# NanoRS485-MySens-v02-25.net
KiCad netlist of a schematic drawn in EAGLE
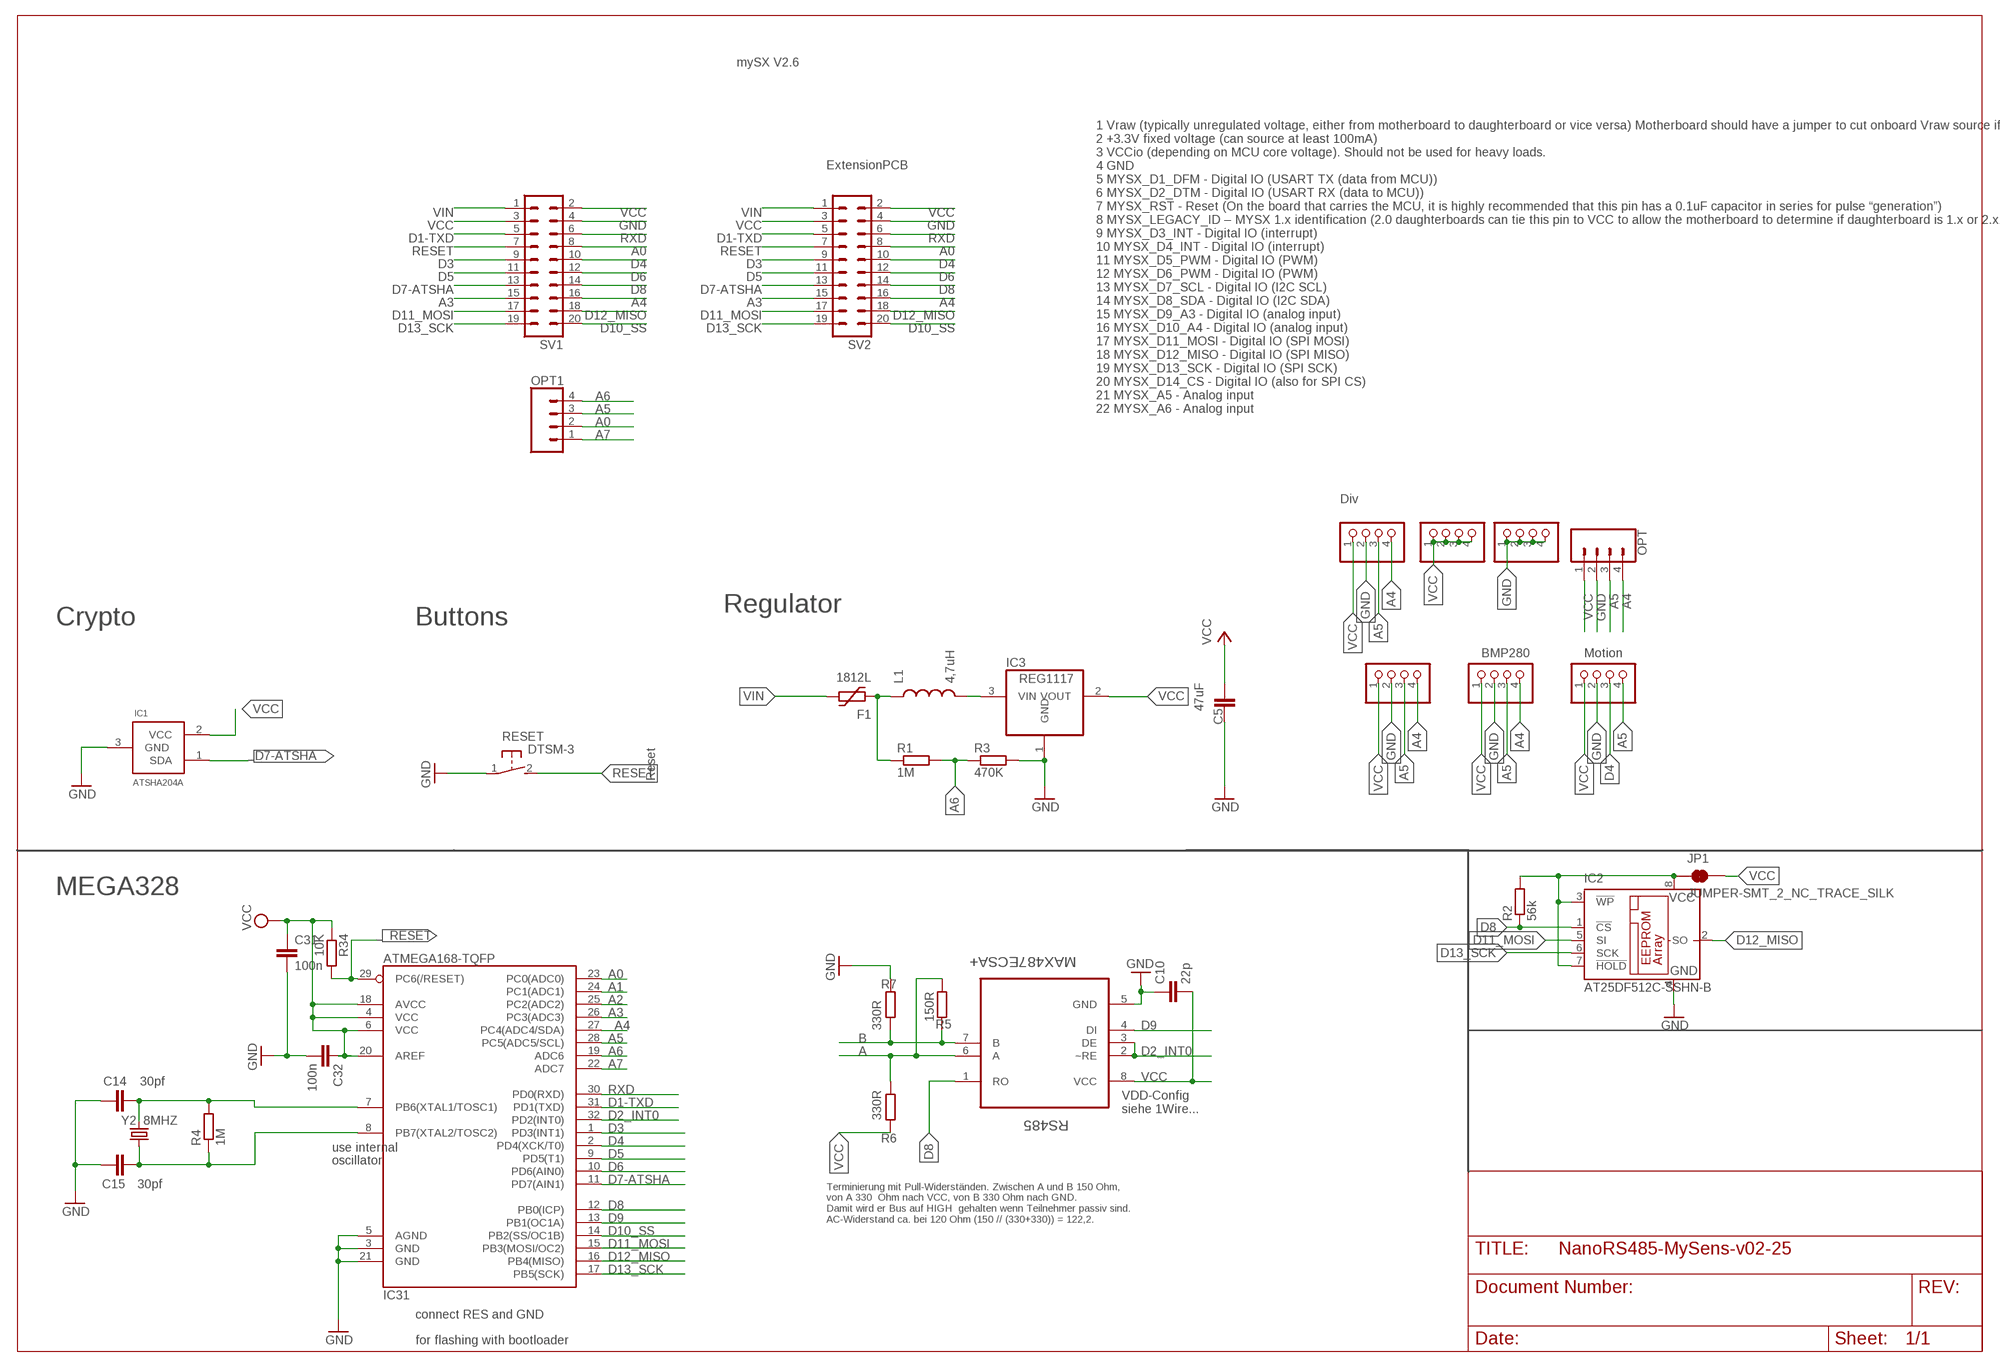
[diagram p0: schematic, sheet 1, part 1 of 2]
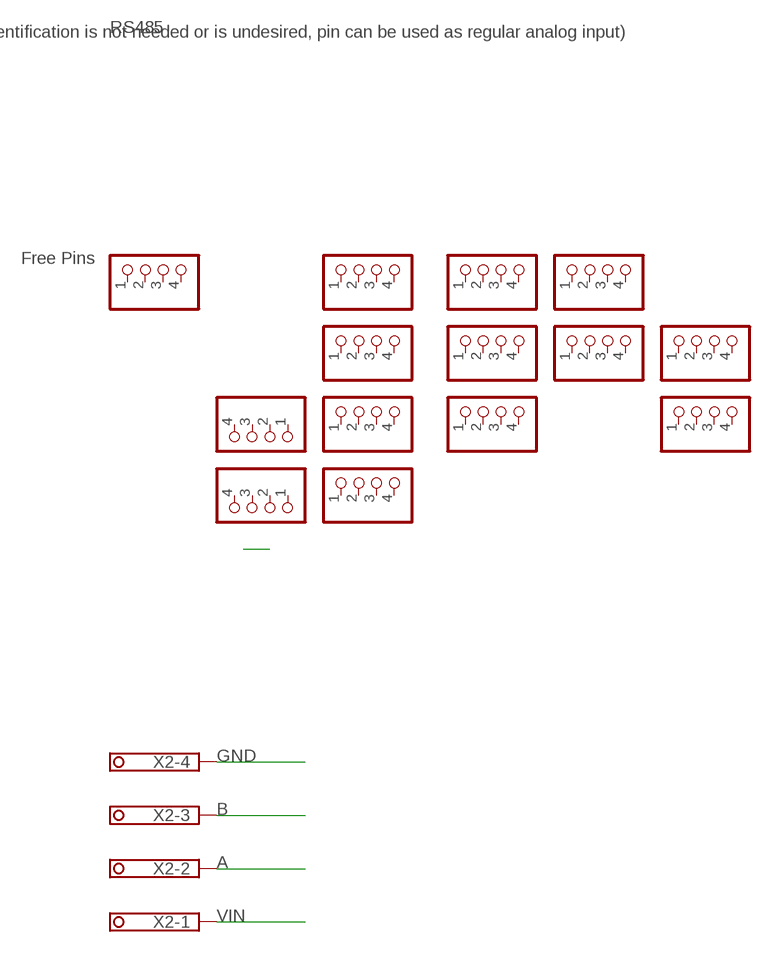
[diagram p1: schematic, sheet 1, part 2 of 2]

(export (version "E")
  (design (tool "Eeschema 10.0.6"))
  (components
    (comp (ref "BH1750")
      (value "PINHD-1X04_2.54-S")
      (footprint "eagle-import:1X04-S")
      (libsource (lib "eagle-import") (part "PINHD-1X04_2.54-S"))
    )
    (comp (ref "C5")
      (value "47uF")
      (footprint "eagle-import:C1210")
      (libsource (lib "eagle-import") (part "C-EUC1210"))
    )
    (comp (ref "C10")
      (value "22p")
      (footprint "eagle-import:C0805")
      (libsource (lib "eagle-import") (part "C-EUC0805"))
    )
    (comp (ref "C14")
      (value "30pf")
      (footprint "eagle-import:0805")
      (libsource (lib "eagle-import") (part "CAP0805"))
    )
    (comp (ref "C15")
      (value "30pf")
      (footprint "eagle-import:0805")
      (libsource (lib "eagle-import") (part "CAP0805"))
    )
    (comp (ref "C31")
      (value "100n")
      (footprint "eagle-import:C0805")
      (libsource (lib "eagle-import") (part "C-EUC0805"))
    )
    (comp (ref "C32")
      (value "100n")
      (footprint "eagle-import:C0805")
      (libsource (lib "eagle-import") (part "C-EUC0805"))
    )
    (comp (ref "F1")
      (value "1812L")
      (footprint "eagle-import:1812L")
      (libsource (lib "eagle-import") (part "1812L"))
    )
    (comp (ref "I2C-1")
      (value "PINHD-1X04_2.54-S")
      (footprint "eagle-import:1X04-S")
      (libsource (lib "eagle-import") (part "PINHD-1X04_2.54-S"))
    )
    (comp (ref "I2C-2")
      (value "PINHD-1X04_2.54-S")
      (footprint "eagle-import:1X04-S")
      (libsource (lib "eagle-import") (part "PINHD-1X04_2.54-S"))
    )
    (comp (ref "IC1")
      (value "ATSHA204A")
      (footprint "eagle-import:SOT23")
      (libsource (lib "eagle-import") (part "ATSHA204A"))
    )
    (comp (ref "IC2")
      (value "AT25DF512C-SSHN-B")
      (footprint "eagle-import:SO-08")
      (fields (field (name "MF") "MICROCHIP") (field (name "MPN") "25AA080/SN"))
      (libsource (lib "eagle-import") (part "25SNAA080"))
    )
    (comp (ref "IC3")
      (value "REG1117")
      (footprint "eagle-import:SOT223")
      (libsource (lib "eagle-import") (part "REG1117"))
    )
    (comp (ref "IC31")
      (value "ATMEGA168-TQFP")
      (footprint "eagle-import:TQFP32-08")
      (libsource (lib "eagle-import") (part "ATMEGA168-TQFP"))
    )
    (comp (ref "JP1")
      (value "JUMPER-SMT_2_NC_TRACE_SILK")
      (footprint "eagle-import:SMT-JUMPER_2_NC_TRACE_SILK")
      (libsource (lib "eagle-import") (part "JUMPER-SMT_2_NC_TRACE_SILK"))
    )
    (comp (ref "JP2")
      (value "PINHD-1X04_2.54-S")
      (footprint "eagle-import:1X04-S")
      (libsource (lib "eagle-import") (part "PINHD-1X04_2.54-S"))
    )
    (comp (ref "JP3")
      (value "PINHD-1X04_2.54-S")
      (footprint "eagle-import:1X04-S")
      (libsource (lib "eagle-import") (part "PINHD-1X04_2.54-S"))
    )
    (comp (ref "JP5")
      (value "PINHD-1X04_2.54-S")
      (footprint "eagle-import:1X04-S")
      (libsource (lib "eagle-import") (part "PINHD-1X04_2.54-S"))
    )
    (comp (ref "JP6")
      (value "PINHD-1X04_2.54-S")
      (footprint "eagle-import:1X04-S")
      (libsource (lib "eagle-import") (part "PINHD-1X04_2.54-S"))
    )
    (comp (ref "JP7")
      (value "PINHD-1X04_2.54-S")
      (footprint "eagle-import:1X04-S")
      (libsource (lib "eagle-import") (part "PINHD-1X04_2.54-S"))
    )
    (comp (ref "JP8")
      (value "PINHD-1X04_2.54-S")
      (footprint "eagle-import:1X04-S")
      (libsource (lib "eagle-import") (part "PINHD-1X04_2.54-S"))
    )
    (comp (ref "JP10")
      (value "PINHD-1X04_2.54-S")
      (footprint "eagle-import:1X04-S")
      (libsource (lib "eagle-import") (part "PINHD-1X04_2.54-S"))
    )
    (comp (ref "JP13")
      (value "PINHD-1X04_2.54-S")
      (footprint "eagle-import:1X04-S")
      (libsource (lib "eagle-import") (part "PINHD-1X04_2.54-S"))
    )
    (comp (ref "JP14")
      (value "PINHD-1X04_2.54-S")
      (footprint "eagle-import:1X04-S")
      (libsource (lib "eagle-import") (part "PINHD-1X04_2.54-S"))
    )
    (comp (ref "JP15")
      (value "PINHD-1X04_2.54-S")
      (footprint "eagle-import:1X04-S")
      (libsource (lib "eagle-import") (part "PINHD-1X04_2.54-S"))
    )
    (comp (ref "JP16")
      (value "PINHD-1X04_2.54-S")
      (footprint "eagle-import:1X04-S")
      (libsource (lib "eagle-import") (part "PINHD-1X04_2.54-S"))
    )
    (comp (ref "JP18")
      (value "PINHD-1X04_2.54-S")
      (footprint "eagle-import:1X04-S")
      (libsource (lib "eagle-import") (part "PINHD-1X04_2.54-S"))
    )
    (comp (ref "JP19")
      (value "PINHD-1X04_2.54-S")
      (footprint "eagle-import:1X04-S")
      (libsource (lib "eagle-import") (part "PINHD-1X04_2.54-S"))
    )
    (comp (ref "JP20")
      (value "PINHD-1X04_2.54-S")
      (footprint "eagle-import:1X04-S")
      (libsource (lib "eagle-import") (part "PINHD-1X04_2.54-S"))
    )
    (comp (ref "JP21")
      (value "PINHD-1X04_2.54-S")
      (footprint "eagle-import:1X04-S")
      (libsource (lib "eagle-import") (part "PINHD-1X04_2.54-S"))
    )
    (comp (ref "JP23")
      (value "PINHD-1X04_2.54-S")
      (footprint "eagle-import:1X04-S")
      (libsource (lib "eagle-import") (part "PINHD-1X04_2.54-S"))
    )
    (comp (ref "L1")
      (value "4,7uH")
      (footprint "eagle-import:0805")
      (libsource (lib "eagle-import") (part "INDUCTOR0805"))
    )
    (comp (ref "MOTION")
      (value "PINHD-1X04_2.54-S")
      (footprint "eagle-import:1X04-S")
      (libsource (lib "eagle-import") (part "PINHD-1X04_2.54-S"))
    )
    (comp (ref "OPT")
      (value "CONN_04")
      (footprint "eagle-import:1X04")
      (libsource (lib "eagle-import") (part "CONN_04"))
    )
    (comp (ref "OPT1")
      (value "CONN_04")
      (footprint "eagle-import:1X04")
      (libsource (lib "eagle-import") (part "CONN_04"))
    )
    (comp (ref "R1")
      (value "1M")
      (footprint "eagle-import:R0805")
      (libsource (lib "eagle-import") (part "R-EU_R0805"))
    )
    (comp (ref "R2")
      (value "56k")
      (footprint "eagle-import:M0805")
      (libsource (lib "eagle-import") (part "resistor_R-EU_M0805"))
    )
    (comp (ref "R3")
      (value "470K")
      (footprint "eagle-import:R0805")
      (libsource (lib "eagle-import") (part "R-EU_R0805"))
    )
    (comp (ref "R4")
      (value "1M")
      (footprint "eagle-import:M0805")
      (libsource (lib "eagle-import") (part "resistor_R-EU_M0805"))
    )
    (comp (ref "R5")
      (value "150R")
      (footprint "eagle-import:R0805")
      (libsource (lib "eagle-import") (part "R-EU_R0805"))
    )
    (comp (ref "R6")
      (value "330R")
      (footprint "eagle-import:R0805")
      (libsource (lib "eagle-import") (part "R-EU_R0805"))
    )
    (comp (ref "R7")
      (value "330R")
      (footprint "eagle-import:R0805")
      (libsource (lib "eagle-import") (part "R-EU_R0805"))
    )
    (comp (ref "R34")
      (value "10K")
      (footprint "eagle-import:R0805")
      (libsource (lib "eagle-import") (part "R-EU_R0805"))
    )
    (comp (ref "RESET")
      (value "DTSM-3")
      (footprint "eagle-import:DTSM-3")
      (libsource (lib "eagle-import") (part "DTSM-3"))
    )
    (comp (ref "RS485")
      (value "MAX487ECSA+")
      (footprint "eagle-import:SOIC127P600X175-8N")
      (libsource (lib "eagle-import") (part "MAX487ECSA+"))
    )
    (comp (ref "SV1")
      (value "MA10-2")
      (footprint "eagle-import:MA10-2")
      (libsource (lib "eagle-import") (part "MA10-2"))
    )
    (comp (ref "SV2")
      (value "MA10-2")
      (footprint "eagle-import:MA10-2")
      (libsource (lib "eagle-import") (part "MA10-2"))
    )
    (comp (ref "X2")
      (value "1751264")
      (footprint "eagle-import:1751264")
      (libsource (lib "eagle-import") (part "1751264"))
    )
    (comp (ref "Y2")
      (value "8MHZ")
      (footprint "eagle-import:CRYSTAL-TXC-7A")
      (libsource (lib "eagle-import") (part "CRYSTALTXC-7A"))
    )
  )
  (nets
    (net (code "1") (name "/A") (class "Default")
      (node (ref "R5") (pin "1") (pinfunction "1_1") (pintype "passive"))
      (node (ref "R6") (pin "2") (pinfunction "2_2") (pintype "passive"))
      (node (ref "RS485") (pin "6") (pinfunction "A_6") (pintype "bidirectional"))
      (node (ref "X2") (pin "2") (pinfunction "K_2") (pintype "passive"))
    )
    (net (code "2") (name "/A0") (class "Default")
      (node (ref "IC31") (pin "23") (pinfunction "PC0(ADC0)_23") (pintype "bidirectional"))
      (node (ref "OPT1") (pin "2") (pinfunction "2_2") (pintype "passive"))
      (node (ref "SV1") (pin "8") (pinfunction "8_8") (pintype "passive"))
      (node (ref "SV2") (pin "8") (pinfunction "8_8") (pintype "passive"))
    )
    (net (code "3") (name "/A1") (class "Default")
      (node (ref "IC31") (pin "24") (pinfunction "PC1(ADC1)_24") (pintype "bidirectional"))
    )
    (net (code "4") (name "/A2") (class "Default")
      (node (ref "IC31") (pin "25") (pinfunction "PC2(ADC2)_25") (pintype "bidirectional"))
    )
    (net (code "5") (name "/A3") (class "Default")
      (node (ref "IC31") (pin "26") (pinfunction "PC3(ADC3)_26") (pintype "bidirectional"))
      (node (ref "SV1") (pin "15") (pinfunction "15_15") (pintype "passive"))
      (node (ref "SV2") (pin "15") (pinfunction "15_15") (pintype "passive"))
    )
    (net (code "6") (name "/A7") (class "Default")
      (node (ref "IC31") (pin "22") (pinfunction "ADC7_22") (pintype "bidirectional"))
      (node (ref "OPT1") (pin "1") (pinfunction "1_1") (pintype "passive"))
    )
    (net (code "7") (name "/B") (class "Default")
      (node (ref "R5") (pin "2") (pinfunction "2_2") (pintype "passive"))
      (node (ref "R7") (pin "1") (pinfunction "1_1") (pintype "passive"))
      (node (ref "RS485") (pin "7") (pinfunction "B_7") (pintype "bidirectional"))
      (node (ref "X2") (pin "3") (pinfunction "K_3") (pintype "passive"))
    )
    (net (code "8") (name "/D1-TXD") (class "Default")
      (node (ref "IC31") (pin "31") (pinfunction "PD1(TXD)_31") (pintype "bidirectional"))
      (node (ref "SV1") (pin "5") (pinfunction "5_5") (pintype "passive"))
      (node (ref "SV2") (pin "5") (pinfunction "5_5") (pintype "passive"))
    )
    (net (code "9") (name "/D2_INT0") (class "Default")
      (node (ref "IC31") (pin "32") (pinfunction "PD2(INT0)_32") (pintype "bidirectional"))
      (node (ref "RS485") (pin "2") (pinfunction "~{RE}_2") (pintype "input"))
      (node (ref "RS485") (pin "3") (pinfunction "DE_3") (pintype "input"))
    )
    (net (code "10") (name "/D3") (class "Default")
      (node (ref "IC31") (pin "1") (pinfunction "PD3(INT1)_1") (pintype "bidirectional"))
      (node (ref "SV1") (pin "9") (pinfunction "9_9") (pintype "passive"))
      (node (ref "SV2") (pin "9") (pinfunction "9_9") (pintype "passive"))
    )
    (net (code "11") (name "/D5") (class "Default")
      (node (ref "IC31") (pin "9") (pinfunction "PD5(T1)_9") (pintype "bidirectional"))
      (node (ref "SV1") (pin "11") (pinfunction "11_11") (pintype "passive"))
      (node (ref "SV2") (pin "11") (pinfunction "11_11") (pintype "passive"))
    )
    (net (code "12") (name "/D6") (class "Default")
      (node (ref "IC31") (pin "10") (pinfunction "PD6(AIN0)_10") (pintype "bidirectional"))
      (node (ref "SV1") (pin "12") (pinfunction "12_12") (pintype "passive"))
      (node (ref "SV2") (pin "12") (pinfunction "12_12") (pintype "passive"))
    )
    (net (code "13") (name "/D7-ATSHA") (class "Default")
      (node (ref "IC1") (pin "1") (pinfunction "SDA_1") (pintype "bidirectional"))
      (node (ref "IC31") (pin "11") (pinfunction "PD7(AIN1)_11") (pintype "bidirectional"))
      (node (ref "SV1") (pin "13") (pinfunction "13_13") (pintype "passive"))
      (node (ref "SV2") (pin "13") (pinfunction "13_13") (pintype "passive"))
    )
    (net (code "14") (name "/D9") (class "Default")
      (node (ref "IC31") (pin "13") (pinfunction "PB1(OC1A)_13") (pintype "bidirectional"))
      (node (ref "RS485") (pin "4") (pinfunction "DI_4") (pintype "input"))
    )
    (net (code "15") (name "/D10_SS") (class "Default")
      (node (ref "IC31") (pin "14") (pinfunction "PB2(SS/OC1B)_14") (pintype "bidirectional"))
      (node (ref "SV1") (pin "20") (pinfunction "20_20") (pintype "passive"))
      (node (ref "SV2") (pin "20") (pinfunction "20_20") (pintype "passive"))
    )
    (net (code "16") (name "/RXD") (class "Default")
      (node (ref "IC31") (pin "30") (pinfunction "PD0(RXD)_30") (pintype "bidirectional"))
      (node (ref "SV1") (pin "6") (pinfunction "6_6") (pintype "passive"))
      (node (ref "SV2") (pin "6") (pinfunction "6_6") (pintype "passive"))
    )
    (net (code "17") (name "A4") (class "Default")
      (node (ref "BH1750") (pin "4") (pinfunction "4_4") (pintype "passive"))
      (node (ref "I2C-1") (pin "4") (pinfunction "4_4") (pintype "passive"))
      (node (ref "I2C-2") (pin "4") (pinfunction "4_4") (pintype "passive"))
      (node (ref "IC31") (pin "27") (pinfunction "PC4(ADC4/SDA)_27") (pintype "bidirectional"))
      (node (ref "OPT") (pin "4") (pinfunction "4_4") (pintype "passive"))
      (node (ref "SV1") (pin "16") (pinfunction "16_16") (pintype "passive"))
      (node (ref "SV2") (pin "16") (pinfunction "16_16") (pintype "passive"))
    )
    (net (code "18") (name "A5") (class "Default")
      (node (ref "BH1750") (pin "3") (pinfunction "3_3") (pintype "passive"))
      (node (ref "I2C-1") (pin "3") (pinfunction "3_3") (pintype "passive"))
      (node (ref "I2C-2") (pin "3") (pinfunction "3_3") (pintype "passive"))
      (node (ref "IC31") (pin "28") (pinfunction "PC5(ADC5/SCL)_28") (pintype "bidirectional"))
      (node (ref "MOTION") (pin "4") (pinfunction "4_4") (pintype "passive"))
      (node (ref "OPT") (pin "3") (pinfunction "3_3") (pintype "passive"))
      (node (ref "OPT1") (pin "3") (pinfunction "3_3") (pintype "passive"))
    )
    (net (code "19") (name "A6") (class "Default")
      (node (ref "IC31") (pin "19") (pinfunction "ADC6_19") (pintype "bidirectional"))
      (node (ref "OPT1") (pin "4") (pinfunction "4_4") (pintype "passive"))
      (node (ref "R1") (pin "2") (pinfunction "2_2") (pintype "passive"))
      (node (ref "R3") (pin "1") (pinfunction "1_1") (pintype "passive"))
    )
    (net (code "20") (name "D4") (class "Default")
      (node (ref "IC31") (pin "2") (pinfunction "PD4(XCK/T0)_2") (pintype "bidirectional"))
      (node (ref "MOTION") (pin "3") (pinfunction "3_3") (pintype "passive"))
      (node (ref "SV1") (pin "10") (pinfunction "10_10") (pintype "passive"))
      (node (ref "SV2") (pin "10") (pinfunction "10_10") (pintype "passive"))
    )
    (net (code "21") (name "D8") (class "Default")
      (node (ref "IC2") (pin "1") (pinfunction "~{CS}_1") (pintype "input"))
      (node (ref "IC31") (pin "12") (pinfunction "PB0(ICP)_12") (pintype "bidirectional"))
      (node (ref "R2") (pin "1") (pinfunction "1_1") (pintype "passive"))
      (node (ref "RS485") (pin "1") (pinfunction "RO_1") (pintype "output"))
      (node (ref "SV1") (pin "14") (pinfunction "14_14") (pintype "passive"))
      (node (ref "SV2") (pin "14") (pinfunction "14_14") (pintype "passive"))
    )
    (net (code "22") (name "D11_MOSI") (class "Default")
      (node (ref "IC2") (pin "5") (pinfunction "SI_5") (pintype "input"))
      (node (ref "IC31") (pin "15") (pinfunction "PB3(MOSI/OC2)_15") (pintype "bidirectional"))
      (node (ref "SV1") (pin "17") (pinfunction "17_17") (pintype "passive"))
      (node (ref "SV2") (pin "17") (pinfunction "17_17") (pintype "passive"))
    )
    (net (code "23") (name "D12_MISO") (class "Default")
      (node (ref "IC2") (pin "2") (pinfunction "SO_2") (pintype "bidirectional"))
      (node (ref "IC31") (pin "16") (pinfunction "PB4(MISO)_16") (pintype "bidirectional"))
      (node (ref "SV1") (pin "18") (pinfunction "18_18") (pintype "passive"))
      (node (ref "SV2") (pin "18") (pinfunction "18_18") (pintype "passive"))
    )
    (net (code "24") (name "D13_SCK") (class "Default")
      (node (ref "IC2") (pin "6") (pinfunction "SCK_6") (pintype "input"))
      (node (ref "IC31") (pin "17") (pinfunction "PB5(SCK)_17") (pintype "bidirectional"))
      (node (ref "SV1") (pin "19") (pinfunction "19_19") (pintype "passive"))
      (node (ref "SV2") (pin "19") (pinfunction "19_19") (pintype "passive"))
    )
    (net (code "25") (name "GND") (class "Default")
      (node (ref "BH1750") (pin "2") (pinfunction "2_2") (pintype "passive"))
      (node (ref "C10") (pin "1") (pinfunction "1_1") (pintype "passive"))
      (node (ref "C14") (pin "1") (pinfunction "1_1") (pintype "passive"))
      (node (ref "C15") (pin "1") (pinfunction "1_1") (pintype "passive"))
      (node (ref "C31") (pin "2") (pinfunction "2_2") (pintype "passive"))
      (node (ref "C32") (pin "2") (pinfunction "2_2") (pintype "passive"))
      (node (ref "C5") (pin "1") (pinfunction "1_1") (pintype "passive"))
      (node (ref "I2C-1") (pin "2") (pinfunction "2_2") (pintype "passive"))
      (node (ref "I2C-2") (pin "2") (pinfunction "2_2") (pintype "passive"))
      (node (ref "IC1") (pin "3") (pinfunction "GND_3") (pintype "bidirectional"))
      (node (ref "IC2") (pin "4") (pinfunction "GND_4") (pintype "power_in"))
      (node (ref "IC3") (pin "1") (pinfunction "GND_1") (pintype "power_in"))
      (node (ref "IC31") (pin "21") (pinfunction "GND_21") (pintype "bidirectional"))
      (node (ref "IC31") (pin "3") (pinfunction "GND_3") (pintype "bidirectional"))
      (node (ref "IC31") (pin "5") (pinfunction "AGND_5") (pintype "bidirectional"))
      (node (ref "JP2") (pin "1") (pinfunction "1_1") (pintype "passive"))
      (node (ref "JP2") (pin "2") (pinfunction "2_2") (pintype "passive"))
      (node (ref "JP2") (pin "3") (pinfunction "3_3") (pintype "passive"))
      (node (ref "JP2") (pin "4") (pinfunction "4_4") (pintype "passive"))
      (node (ref "MOTION") (pin "2") (pinfunction "2_2") (pintype "passive"))
      (node (ref "OPT") (pin "2") (pinfunction "2_2") (pintype "passive"))
      (node (ref "R3") (pin "2") (pinfunction "2_2") (pintype "passive"))
      (node (ref "R7") (pin "2") (pinfunction "2_2") (pintype "passive"))
      (node (ref "RESET") (pin "1") (pinfunction "1_1") (pintype "passive"))
      (node (ref "RS485") (pin "5") (pinfunction "GND_5") (pintype "passive"))
      (node (ref "SV1") (pin "4") (pinfunction "4_4") (pintype "passive"))
      (node (ref "SV2") (pin "4") (pinfunction "4_4") (pintype "passive"))
      (node (ref "X2") (pin "4") (pinfunction "K_4") (pintype "passive"))
    )
    (net (code "26") (name "Net-(F1-1)") (class "Default")
      (node (ref "F1") (pin "P$1") (pinfunction "1_P$1") (pintype "passive"))
      (node (ref "L1") (pin "1") (pinfunction "1_1") (pintype "passive"))
      (node (ref "R1") (pin "1") (pinfunction "1_1") (pintype "passive"))
    )
    (net (code "27") (name "Net-(IC2-VCC)") (class "Default")
      (node (ref "IC2") (pin "3") (pinfunction "~{WP}_3") (pintype "input"))
      (node (ref "IC2") (pin "7") (pinfunction "~{HOLD}_7") (pintype "input"))
      (node (ref "IC2") (pin "8") (pinfunction "VCC_8") (pintype "power_in"))
      (node (ref "JP1") (pin "1") (pinfunction "1_1") (pintype "passive"))
      (node (ref "R2") (pin "2") (pinfunction "2_2") (pintype "passive"))
    )
    (net (code "28") (name "Net-(IC3-VIN)") (class "Default")
      (node (ref "IC3") (pin "3") (pinfunction "VIN_3") (pintype "input"))
      (node (ref "L1") (pin "2") (pinfunction "2_2") (pintype "passive"))
    )
    (net (code "29") (name "Net-(IC31-PB6(XTAL1{slash}TOSC1))") (class "Default")
      (node (ref "C14") (pin "2") (pinfunction "2_2") (pintype "passive"))
      (node (ref "IC31") (pin "7") (pinfunction "PB6(XTAL1/TOSC1)_7") (pintype "bidirectional"))
      (node (ref "R4") (pin "2") (pinfunction "2_2") (pintype "passive"))
      (node (ref "Y2") (pin "P$2") (pinfunction "2_P$2") (pintype "passive"))
    )
    (net (code "30") (name "Net-(IC31-PB7(XTAL2{slash}TOSC2))") (class "Default")
      (node (ref "C15") (pin "2") (pinfunction "2_2") (pintype "passive"))
      (node (ref "IC31") (pin "8") (pinfunction "PB7(XTAL2/TOSC2)_8") (pintype "bidirectional"))
      (node (ref "R4") (pin "1") (pinfunction "1_1") (pintype "passive"))
      (node (ref "Y2") (pin "P$1") (pinfunction "1_P$1") (pintype "passive"))
    )
    (net (code "31") (name "RESET") (class "Default")
      (node (ref "IC31") (pin "29") (pinfunction "PC6(/RESET)_29") (pintype "bidirectional"))
      (node (ref "R34") (pin "2") (pinfunction "2_2") (pintype "passive"))
      (node (ref "RESET") (pin "2") (pinfunction "2_2") (pintype "passive"))
      (node (ref "SV1") (pin "7") (pinfunction "7_7") (pintype "passive"))
      (node (ref "SV2") (pin "7") (pinfunction "7_7") (pintype "passive"))
    )
    (net (code "32") (name "VCC") (class "Default")
      (node (ref "BH1750") (pin "1") (pinfunction "1_1") (pintype "passive"))
      (node (ref "C10") (pin "2") (pinfunction "2_2") (pintype "passive"))
      (node (ref "C31") (pin "1") (pinfunction "1_1") (pintype "passive"))
      (node (ref "C32") (pin "1") (pinfunction "1_1") (pintype "passive"))
      (node (ref "C5") (pin "2") (pinfunction "2_2") (pintype "passive"))
      (node (ref "I2C-1") (pin "1") (pinfunction "1_1") (pintype "passive"))
      (node (ref "I2C-2") (pin "1") (pinfunction "1_1") (pintype "passive"))
      (node (ref "IC1") (pin "2") (pinfunction "VCC_2") (pintype "bidirectional"))
      (node (ref "IC3") (pin "2") (pinfunction "VOUT_2") (pintype "output"))
      (node (ref "IC31") (pin "18") (pinfunction "AVCC_18") (pintype "bidirectional"))
      (node (ref "IC31") (pin "20") (pinfunction "AREF_20") (pintype "bidirectional"))
      (node (ref "IC31") (pin "4") (pinfunction "VCC_4") (pintype "bidirectional"))
      (node (ref "IC31") (pin "6") (pinfunction "VCC_6") (pintype "bidirectional"))
      (node (ref "JP1") (pin "2") (pinfunction "2_2") (pintype "passive"))
      (node (ref "JP3") (pin "1") (pinfunction "1_1") (pintype "passive"))
      (node (ref "JP3") (pin "2") (pinfunction "2_2") (pintype "passive"))
      (node (ref "JP3") (pin "3") (pinfunction "3_3") (pintype "passive"))
      (node (ref "JP3") (pin "4") (pinfunction "4_4") (pintype "passive"))
      (node (ref "MOTION") (pin "1") (pinfunction "1_1") (pintype "passive"))
      (node (ref "OPT") (pin "1") (pinfunction "1_1") (pintype "passive"))
      (node (ref "R34") (pin "1") (pinfunction "1_1") (pintype "passive"))
      (node (ref "R6") (pin "1") (pinfunction "1_1") (pintype "passive"))
      (node (ref "RS485") (pin "8") (pinfunction "VCC_8") (pintype "power_in"))
      (node (ref "SV1") (pin "2") (pinfunction "2_2") (pintype "passive"))
      (node (ref "SV1") (pin "3") (pinfunction "3_3") (pintype "passive"))
      (node (ref "SV2") (pin "2") (pinfunction "2_2") (pintype "passive"))
      (node (ref "SV2") (pin "3") (pinfunction "3_3") (pintype "passive"))
    )
    (net (code "33") (name "VIN") (class "Default")
      (node (ref "F1") (pin "P$2") (pinfunction "2_P$2") (pintype "passive"))
      (node (ref "SV1") (pin "1") (pinfunction "1_1") (pintype "passive"))
      (node (ref "SV2") (pin "1") (pinfunction "1_1") (pintype "passive"))
      (node (ref "X2") (pin "1") (pinfunction "K_1") (pintype "passive"))
    )
    (net (code "34") (name "unconnected-(JP5-Pad1)") (class "Default")
      (node (ref "JP5") (pin "1") (pinfunction "1_1") (pintype "passive"))
    )
    (net (code "35") (name "unconnected-(JP5-Pad2)") (class "Default")
      (node (ref "JP5") (pin "2") (pinfunction "2_2") (pintype "passive"))
    )
    (net (code "36") (name "unconnected-(JP5-Pad3)") (class "Default")
      (node (ref "JP5") (pin "3") (pinfunction "3_3") (pintype "passive"))
    )
    (net (code "37") (name "unconnected-(JP5-Pad4)") (class "Default")
      (node (ref "JP5") (pin "4") (pinfunction "4_4") (pintype "passive"))
    )
    (net (code "38") (name "unconnected-(JP6-Pad1)") (class "Default")
      (node (ref "JP6") (pin "1") (pinfunction "1_1") (pintype "passive"))
    )
    (net (code "39") (name "unconnected-(JP6-Pad2)") (class "Default")
      (node (ref "JP6") (pin "2") (pinfunction "2_2") (pintype "passive"))
    )
    (net (code "40") (name "unconnected-(JP6-Pad3)") (class "Default")
      (node (ref "JP6") (pin "3") (pinfunction "3_3") (pintype "passive"))
    )
    (net (code "41") (name "unconnected-(JP6-Pad4)") (class "Default")
      (node (ref "JP6") (pin "4") (pinfunction "4_4") (pintype "passive"))
    )
    (net (code "42") (name "unconnected-(JP7-Pad1)") (class "Default")
      (node (ref "JP7") (pin "1") (pinfunction "1_1") (pintype "passive"))
    )
    (net (code "43") (name "unconnected-(JP7-Pad2)") (class "Default")
      (node (ref "JP7") (pin "2") (pinfunction "2_2") (pintype "passive"))
    )
    (net (code "44") (name "unconnected-(JP7-Pad3)") (class "Default")
      (node (ref "JP7") (pin "3") (pinfunction "3_3") (pintype "passive"))
    )
    (net (code "45") (name "unconnected-(JP7-Pad4)") (class "Default")
      (node (ref "JP7") (pin "4") (pinfunction "4_4") (pintype "passive"))
    )
    (net (code "46") (name "unconnected-(JP8-Pad1)") (class "Default")
      (node (ref "JP8") (pin "1") (pinfunction "1_1") (pintype "passive"))
    )
    (net (code "47") (name "unconnected-(JP8-Pad2)") (class "Default")
      (node (ref "JP8") (pin "2") (pinfunction "2_2") (pintype "passive"))
    )
    (net (code "48") (name "unconnected-(JP8-Pad3)") (class "Default")
      (node (ref "JP8") (pin "3") (pinfunction "3_3") (pintype "passive"))
    )
    (net (code "49") (name "unconnected-(JP8-Pad4)") (class "Default")
      (node (ref "JP8") (pin "4") (pinfunction "4_4") (pintype "passive"))
    )
    (net (code "50") (name "unconnected-(JP10-Pad1)") (class "Default")
      (node (ref "JP10") (pin "1") (pinfunction "1_1") (pintype "passive"))
    )
    (net (code "51") (name "unconnected-(JP10-Pad2)") (class "Default")
      (node (ref "JP10") (pin "2") (pinfunction "2_2") (pintype "passive"))
    )
    (net (code "52") (name "unconnected-(JP10-Pad3)") (class "Default")
      (node (ref "JP10") (pin "3") (pinfunction "3_3") (pintype "passive"))
    )
    (net (code "53") (name "unconnected-(JP10-Pad4)") (class "Default")
      (node (ref "JP10") (pin "4") (pinfunction "4_4") (pintype "passive"))
    )
    (net (code "54") (name "unconnected-(JP13-Pad1)") (class "Default")
      (node (ref "JP13") (pin "1") (pinfunction "1_1") (pintype "passive"))
    )
    (net (code "55") (name "unconnected-(JP13-Pad2)") (class "Default")
      (node (ref "JP13") (pin "2") (pinfunction "2_2") (pintype "passive"))
    )
    (net (code "56") (name "unconnected-(JP13-Pad3)") (class "Default")
      (node (ref "JP13") (pin "3") (pinfunction "3_3") (pintype "passive"))
    )
    (net (code "57") (name "unconnected-(JP13-Pad4)") (class "Default")
      (node (ref "JP13") (pin "4") (pinfunction "4_4") (pintype "passive"))
    )
    (net (code "58") (name "unconnected-(JP14-Pad1)") (class "Default")
      (node (ref "JP14") (pin "1") (pinfunction "1_1") (pintype "passive"))
    )
    (net (code "59") (name "unconnected-(JP14-Pad2)") (class "Default")
      (node (ref "JP14") (pin "2") (pinfunction "2_2") (pintype "passive"))
    )
    (net (code "60") (name "unconnected-(JP14-Pad3)") (class "Default")
      (node (ref "JP14") (pin "3") (pinfunction "3_3") (pintype "passive"))
    )
    (net (code "61") (name "unconnected-(JP14-Pad4)") (class "Default")
      (node (ref "JP14") (pin "4") (pinfunction "4_4") (pintype "passive"))
    )
    (net (code "62") (name "unconnected-(JP15-Pad1)") (class "Default")
      (node (ref "JP15") (pin "1") (pinfunction "1_1") (pintype "passive"))
    )
    (net (code "63") (name "unconnected-(JP15-Pad2)") (class "Default")
      (node (ref "JP15") (pin "2") (pinfunction "2_2") (pintype "passive"))
    )
    (net (code "64") (name "unconnected-(JP15-Pad3)") (class "Default")
      (node (ref "JP15") (pin "3") (pinfunction "3_3") (pintype "passive"))
    )
    (net (code "65") (name "unconnected-(JP15-Pad4)") (class "Default")
      (node (ref "JP15") (pin "4") (pinfunction "4_4") (pintype "passive"))
    )
    (net (code "66") (name "unconnected-(JP16-Pad1)") (class "Default")
      (node (ref "JP16") (pin "1") (pinfunction "1_1") (pintype "passive"))
    )
    (net (code "67") (name "unconnected-(JP16-Pad2)") (class "Default")
      (node (ref "JP16") (pin "2") (pinfunction "2_2") (pintype "passive"))
    )
    (net (code "68") (name "unconnected-(JP16-Pad3)") (class "Default")
      (node (ref "JP16") (pin "3") (pinfunction "3_3") (pintype "passive"))
    )
    (net (code "69") (name "unconnected-(JP16-Pad4)") (class "Default")
      (node (ref "JP16") (pin "4") (pinfunction "4_4") (pintype "passive"))
    )
    (net (code "70") (name "unconnected-(JP18-Pad1)") (class "Default")
      (node (ref "JP18") (pin "1") (pinfunction "1_1") (pintype "passive"))
    )
    (net (code "71") (name "unconnected-(JP18-Pad2)") (class "Default")
      (node (ref "JP18") (pin "2") (pinfunction "2_2") (pintype "passive"))
    )
    (net (code "72") (name "unconnected-(JP18-Pad3)") (class "Default")
      (node (ref "JP18") (pin "3") (pinfunction "3_3") (pintype "passive"))
    )
    (net (code "73") (name "unconnected-(JP18-Pad4)") (class "Default")
      (node (ref "JP18") (pin "4") (pinfunction "4_4") (pintype "passive"))
    )
    (net (code "74") (name "unconnected-(JP19-Pad1)") (class "Default")
      (node (ref "JP19") (pin "1") (pinfunction "1_1") (pintype "passive"))
    )
    (net (code "75") (name "unconnected-(JP19-Pad2)") (class "Default")
      (node (ref "JP19") (pin "2") (pinfunction "2_2") (pintype "passive"))
    )
    (net (code "76") (name "unconnected-(JP19-Pad3)") (class "Default")
      (node (ref "JP19") (pin "3") (pinfunction "3_3") (pintype "passive"))
    )
    (net (code "77") (name "unconnected-(JP19-Pad4)") (class "Default")
      (node (ref "JP19") (pin "4") (pinfunction "4_4") (pintype "passive"))
    )
    (net (code "78") (name "unconnected-(JP20-Pad1)") (class "Default")
      (node (ref "JP20") (pin "1") (pinfunction "1_1") (pintype "passive"))
    )
    (net (code "79") (name "unconnected-(JP20-Pad2)") (class "Default")
      (node (ref "JP20") (pin "2") (pinfunction "2_2") (pintype "passive"))
    )
    (net (code "80") (name "unconnected-(JP20-Pad3)") (class "Default")
      (node (ref "JP20") (pin "3") (pinfunction "3_3") (pintype "passive"))
    )
    (net (code "81") (name "unconnected-(JP20-Pad4)") (class "Default")
      (node (ref "JP20") (pin "4") (pinfunction "4_4") (pintype "passive"))
    )
    (net (code "82") (name "unconnected-(JP21-Pad1)") (class "Default")
      (node (ref "JP21") (pin "1") (pinfunction "1_1") (pintype "passive"))
    )
    (net (code "83") (name "unconnected-(JP21-Pad2)") (class "Default")
      (node (ref "JP21") (pin "2") (pinfunction "2_2") (pintype "passive"))
    )
    (net (code "84") (name "unconnected-(JP21-Pad3)") (class "Default")
      (node (ref "JP21") (pin "3") (pinfunction "3_3") (pintype "passive"))
    )
    (net (code "85") (name "unconnected-(JP21-Pad4)") (class "Default")
      (node (ref "JP21") (pin "4") (pinfunction "4_4") (pintype "passive"))
    )
    (net (code "86") (name "unconnected-(JP23-Pad1)") (class "Default")
      (node (ref "JP23") (pin "1") (pinfunction "1_1") (pintype "passive"))
    )
    (net (code "87") (name "unconnected-(JP23-Pad2)") (class "Default")
      (node (ref "JP23") (pin "2") (pinfunction "2_2") (pintype "passive"))
    )
    (net (code "88") (name "unconnected-(JP23-Pad3)") (class "Default")
      (node (ref "JP23") (pin "3") (pinfunction "3_3") (pintype "passive"))
    )
    (net (code "89") (name "unconnected-(JP23-Pad4)") (class "Default")
      (node (ref "JP23") (pin "4") (pinfunction "4_4") (pintype "passive"))
    )
  )
)
